# LoRaBBPi.net
KiCad netlist of a schematic drawn in EAGLE
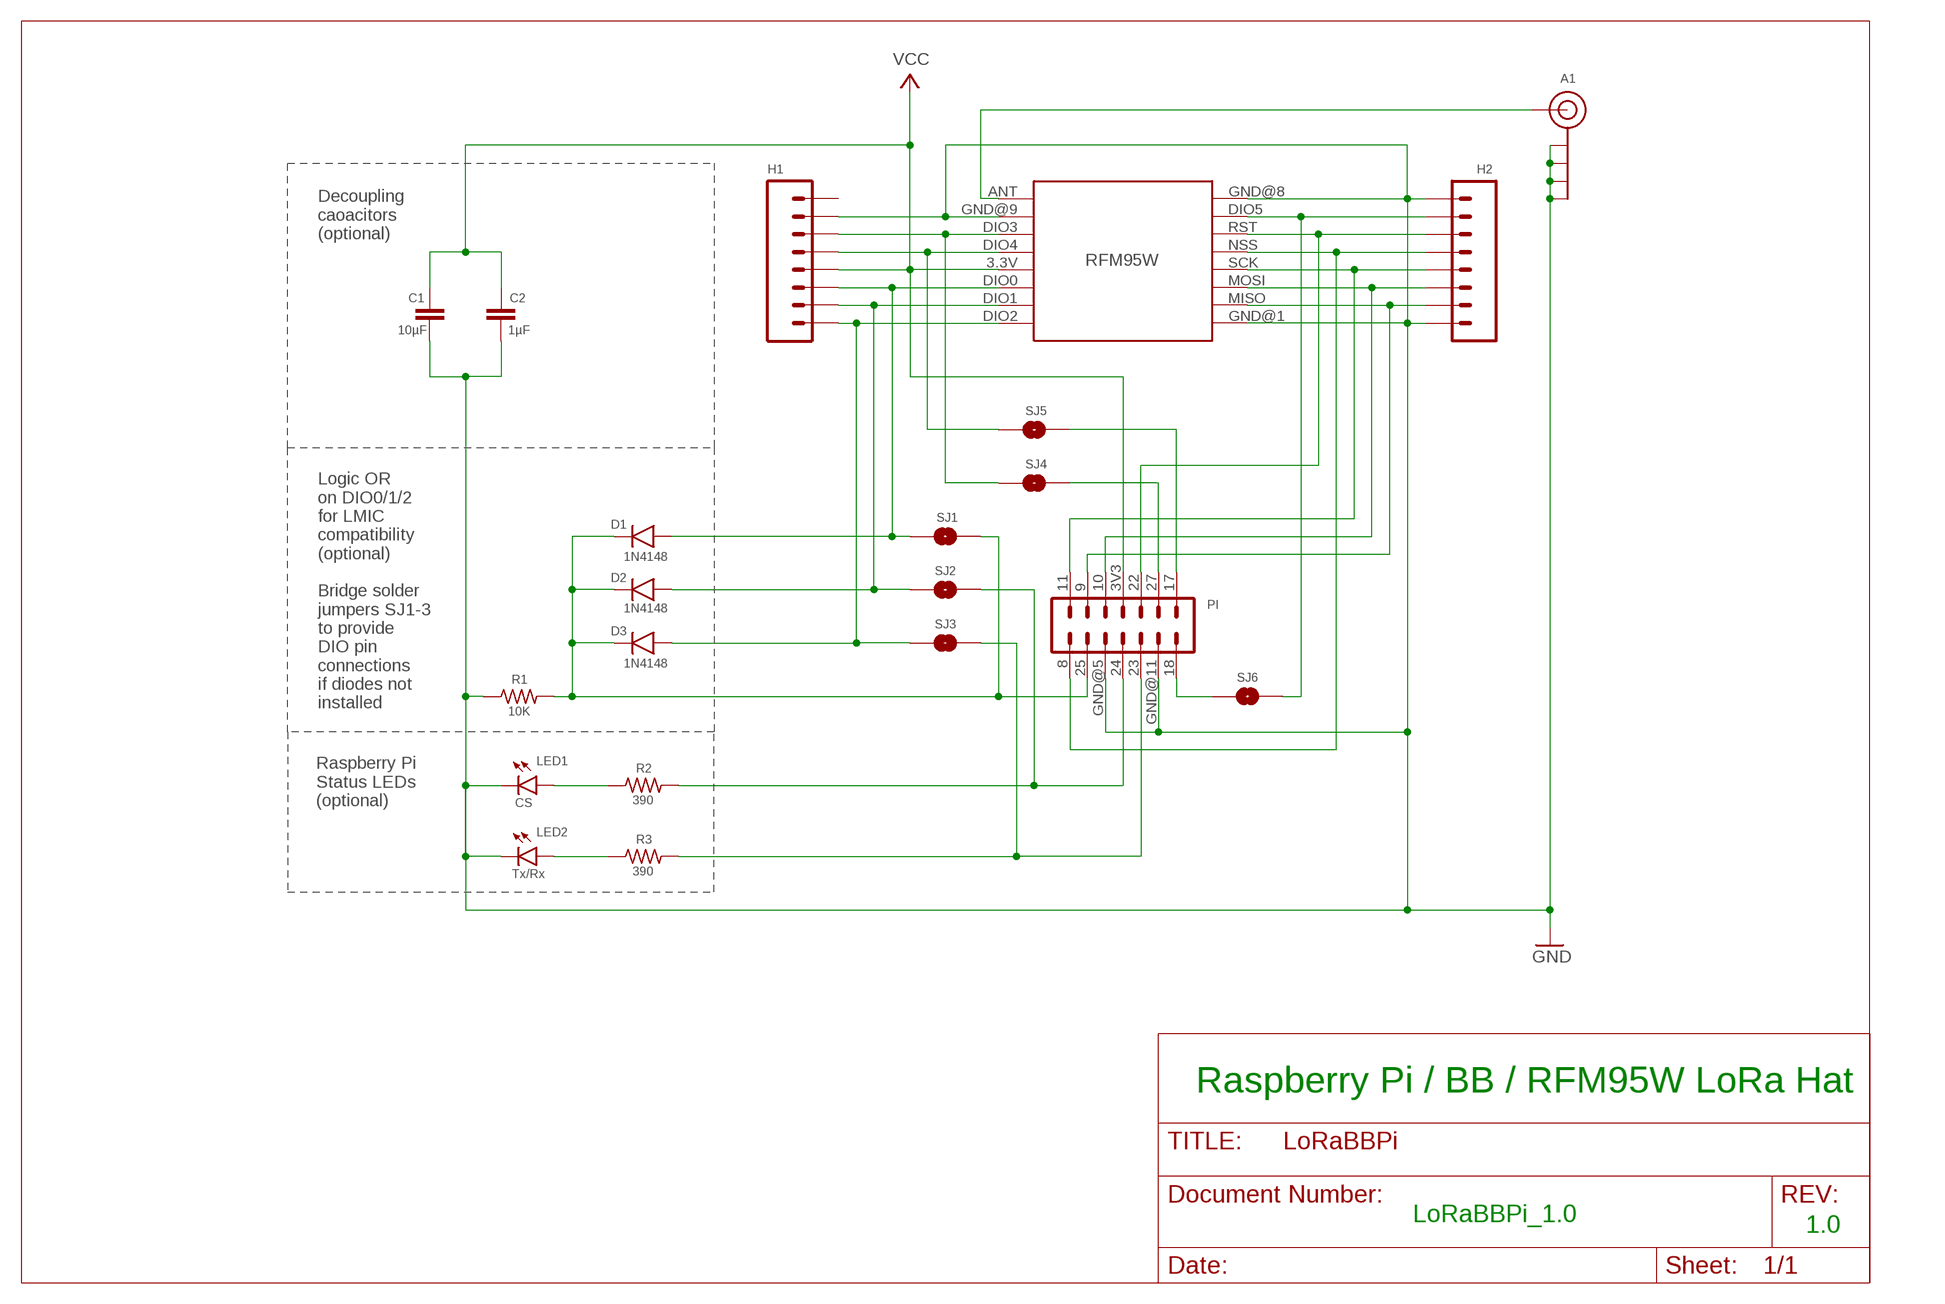
[diagram p0: schematic, sheet 1]

(export (version "E")
  (design (tool "Eeschema 10.0.6"))
  (components
    (comp (ref "A1")
      (value "U.FL-SMA-EDGE-COMBO")
      (footprint "eagle-import:U.FL-SMA-EDGE-COMBO")
      (libsource (lib "eagle-import") (part "U.FL-SMA-EDGE-COMBO"))
    )
    (comp (ref "C1")
      (value "10µF")
      (footprint "eagle-import:C0805")
      (libsource (lib "eagle-import") (part "CAPACITOR"))
    )
    (comp (ref "C2")
      (value "1µF")
      (footprint "eagle-import:C0805")
      (libsource (lib "eagle-import") (part "CAPACITOR"))
    )
    (comp (ref "D1")
      (value "1N4148")
      (footprint "eagle-import:SOD-123")
      (libsource (lib "eagle-import") (part "1N4148SMD"))
    )
    (comp (ref "D2")
      (value "1N4148")
      (footprint "eagle-import:SOD-123")
      (libsource (lib "eagle-import") (part "1N4148SMD"))
    )
    (comp (ref "D3")
      (value "1N4148")
      (footprint "eagle-import:SOD-123")
      (libsource (lib "eagle-import") (part "1N4148SMD"))
    )
    (comp (ref "H1")
      (value "1X8-PIN-HEADER")
      (footprint "eagle-import:1X8")
      (libsource (lib "eagle-import") (part "1X8-PIN-HEADER"))
    )
    (comp (ref "H2")
      (value "1X8-PIN-HEADER")
      (footprint "eagle-import:1X8")
      (libsource (lib "eagle-import") (part "1X8-PIN-HEADER"))
    )
    (comp (ref "LED1")
      (value "CS")
      (footprint "eagle-import:CHIP-LED0805")
      (libsource (lib "eagle-import") (part "LEDCHIP-LED0805"))
    )
    (comp (ref "LED2")
      (value "Tx/Rx")
      (footprint "eagle-import:CHIP-LED0805")
      (libsource (lib "eagle-import") (part "LEDCHIP-LED0805"))
    )
    (comp (ref "PI")
      (value "2X7-PIN-HEADER")
      (footprint "eagle-import:2X7")
      (libsource (lib "eagle-import") (part "2X7-PIN-HEADER"))
    )
    (comp (ref "R1")
      (value "10K")
      (footprint "eagle-import:R0805")
      (libsource (lib "eagle-import") (part "R-US_R0805"))
    )
    (comp (ref "R2")
      (value "390")
      (footprint "eagle-import:R0805")
      (libsource (lib "eagle-import") (part "R-US_R0805"))
    )
    (comp (ref "R3")
      (value "390")
      (footprint "eagle-import:R0805")
      (libsource (lib "eagle-import") (part "R-US_R0805"))
    )
    (comp (ref "RFM95W")
      (value "RFM95W-LORA")
      (footprint "eagle-import:RFM95W-LORA")
      (libsource (lib "eagle-import") (part "RFM95W-LORA"))
    )
    (comp (ref "SJ1") (value "SJ") (footprint "eagle-import:SJ") (libsource (lib "eagle-import") (part "SJ")))
    (comp (ref "SJ2") (value "SJ") (footprint "eagle-import:SJ") (libsource (lib "eagle-import") (part "SJ")))
    (comp (ref "SJ3") (value "SJ") (footprint "eagle-import:SJ") (libsource (lib "eagle-import") (part "SJ")))
    (comp (ref "SJ4") (value "SJ") (footprint "eagle-import:SJ") (libsource (lib "eagle-import") (part "SJ")))
    (comp (ref "SJ5") (value "SJ") (footprint "eagle-import:SJ") (libsource (lib "eagle-import") (part "SJ")))
    (comp (ref "SJ6") (value "SJ") (footprint "eagle-import:SJ") (libsource (lib "eagle-import") (part "SJ")))
  )
  (nets
    (net (code "1") (name "GND") (class "Default")
      (node (ref "A1") (pin "GND@1A") (pinfunction "GND_GND@1A") (pintype "bidirectional"))
      (node (ref "A1") (pin "GND@1B") (pinfunction "GND_GND@1B") (pintype "bidirectional"))
      (node (ref "A1") (pin "GND@2A") (pinfunction "GND_GND@2A") (pintype "bidirectional"))
      (node (ref "A1") (pin "GND@2B") (pinfunction "GND_GND@2B") (pintype "bidirectional"))
      (node (ref "C1") (pin "2") (pinfunction "2_2") (pintype "passive"))
      (node (ref "C2") (pin "2") (pinfunction "2_2") (pintype "passive"))
      (node (ref "H1") (pin "2") (pinfunction "2_2") (pintype "passive"))
      (node (ref "H2") (pin "1") (pinfunction "1_1") (pintype "passive"))
      (node (ref "H2") (pin "8") (pinfunction "8_8") (pintype "passive"))
      (node (ref "LED1") (pin "C") (pinfunction "C_C") (pintype "passive"))
      (node (ref "LED2") (pin "C") (pinfunction "C_C") (pintype "passive"))
      (node (ref "PI") (pin "GND@11") (pinfunction "GND_GND@11") (pintype "passive"))
      (node (ref "PI") (pin "GND@5") (pinfunction "GND_GND@5") (pintype "passive"))
      (node (ref "R1") (pin "1") (pinfunction "1_1") (pintype "passive"))
      (node (ref "RFM95W") (pin "GND@1") (pinfunction "GND.1_GND@1") (pintype "power_in"))
      (node (ref "RFM95W") (pin "GND@8") (pinfunction "GND.2_GND@8") (pintype "power_in"))
      (node (ref "RFM95W") (pin "GND@9") (pinfunction "GND.3_GND@9") (pintype "power_in"))
    )
    (net (code "2") (name "Net-(A1-PadSIG)") (class "Default")
      (node (ref "A1") (pin "SIG") (pinfunction "SIG_SIG") (pintype "bidirectional"))
      (node (ref "RFM95W") (pin "ANT") (pinfunction "ANT_ANT") (pintype "passive"))
    )
    (net (code "3") (name "Net-(D1-Pad1)") (class "Default")
      (node (ref "D1") (pin "1") (pinfunction "1_1") (pintype "bidirectional"))
      (node (ref "D2") (pin "1") (pinfunction "1_1") (pintype "bidirectional"))
      (node (ref "D3") (pin "1") (pinfunction "1_1") (pintype "bidirectional"))
      (node (ref "PI") (pin "25") (pinfunction "25_25") (pintype "passive"))
      (node (ref "R1") (pin "2") (pinfunction "2_2") (pintype "passive"))
      (node (ref "SJ1") (pin "2") (pinfunction "2_2") (pintype "passive"))
    )
    (net (code "4") (name "Net-(D1-Pad2)") (class "Default")
      (node (ref "D1") (pin "2") (pinfunction "2_2") (pintype "bidirectional"))
      (node (ref "H1") (pin "6") (pinfunction "6_6") (pintype "passive"))
      (node (ref "RFM95W") (pin "DIO0") (pinfunction "DIO0_DIO0") (pintype "bidirectional"))
      (node (ref "SJ1") (pin "1") (pinfunction "1_1") (pintype "passive"))
    )
    (net (code "5") (name "Net-(D2-Pad2)") (class "Default")
      (node (ref "D2") (pin "2") (pinfunction "2_2") (pintype "bidirectional"))
      (node (ref "H1") (pin "7") (pinfunction "7_7") (pintype "passive"))
      (node (ref "RFM95W") (pin "DIO1") (pinfunction "DIO1_DIO1") (pintype "bidirectional"))
      (node (ref "SJ2") (pin "1") (pinfunction "1_1") (pintype "passive"))
    )
    (net (code "6") (name "Net-(D3-Pad2)") (class "Default")
      (node (ref "D3") (pin "2") (pinfunction "2_2") (pintype "bidirectional"))
      (node (ref "H1") (pin "8") (pinfunction "8_8") (pintype "passive"))
      (node (ref "RFM95W") (pin "DIO2") (pinfunction "DIO2_DIO2") (pintype "bidirectional"))
      (node (ref "SJ3") (pin "1") (pinfunction "1_1") (pintype "passive"))
    )
    (net (code "7") (name "Net-(H1-Pad3)") (class "Default")
      (node (ref "H1") (pin "3") (pinfunction "3_3") (pintype "passive"))
      (node (ref "RFM95W") (pin "DIO3") (pinfunction "DIO3_DIO3") (pintype "bidirectional"))
      (node (ref "SJ4") (pin "1") (pinfunction "1_1") (pintype "passive"))
    )
    (net (code "8") (name "Net-(H1-Pad4)") (class "Default")
      (node (ref "H1") (pin "4") (pinfunction "4_4") (pintype "passive"))
      (node (ref "RFM95W") (pin "DIO4") (pinfunction "DIO4_DIO4") (pintype "bidirectional"))
      (node (ref "SJ5") (pin "1") (pinfunction "1_1") (pintype "passive"))
    )
    (net (code "9") (name "Net-(H2-Pad2)") (class "Default")
      (node (ref "H2") (pin "2") (pinfunction "2_2") (pintype "passive"))
      (node (ref "RFM95W") (pin "DIO5") (pinfunction "DIO5_DIO5") (pintype "bidirectional"))
      (node (ref "SJ6") (pin "2") (pinfunction "2_2") (pintype "passive"))
    )
    (net (code "10") (name "Net-(H2-Pad5)") (class "Default")
      (node (ref "H2") (pin "5") (pinfunction "5_5") (pintype "passive"))
      (node (ref "PI") (pin "11") (pinfunction "11_11") (pintype "passive"))
      (node (ref "RFM95W") (pin "SCK") (pinfunction "SCK_SCK") (pintype "bidirectional"))
    )
    (net (code "11") (name "Net-(H2-Pad6)") (class "Default")
      (node (ref "H2") (pin "6") (pinfunction "6_6") (pintype "passive"))
      (node (ref "PI") (pin "10") (pinfunction "10_10") (pintype "passive"))
      (node (ref "RFM95W") (pin "MOSI") (pinfunction "MOSI_MOSI") (pintype "bidirectional"))
    )
    (net (code "12") (name "Net-(H2-Pad7)") (class "Default")
      (node (ref "H2") (pin "7") (pinfunction "7_7") (pintype "passive"))
      (node (ref "PI") (pin "9") (pinfunction "9_9") (pintype "passive"))
      (node (ref "RFM95W") (pin "MISO") (pinfunction "MISO_MISO") (pintype "bidirectional"))
    )
    (net (code "13") (name "Net-(LED1-PadA)") (class "Default")
      (node (ref "LED1") (pin "A") (pinfunction "A_A") (pintype "passive"))
      (node (ref "R2") (pin "1") (pinfunction "1_1") (pintype "passive"))
    )
    (net (code "14") (name "Net-(LED2-PadA)") (class "Default")
      (node (ref "LED2") (pin "A") (pinfunction "A_A") (pintype "passive"))
      (node (ref "R3") (pin "1") (pinfunction "1_1") (pintype "passive"))
    )
    (net (code "15") (name "Net-(PI-1)") (class "Default")
      (node (ref "H2") (pin "4") (pinfunction "4_4") (pintype "passive"))
      (node (ref "PI") (pin "8") (pinfunction "1_8") (pintype "passive"))
      (node (ref "RFM95W") (pin "NSS") (pinfunction "NSS_NSS") (pintype "bidirectional"))
    )
    (net (code "16") (name "Net-(PI-22)") (class "Default")
      (node (ref "PI") (pin "27") (pinfunction "22_27") (pintype "passive"))
      (node (ref "SJ4") (pin "2") (pinfunction "2_2") (pintype "passive"))
    )
    (net (code "17") (name "Net-(PI-27)") (class "Default")
      (node (ref "H2") (pin "3") (pinfunction "3_3") (pintype "passive"))
      (node (ref "PI") (pin "22") (pinfunction "27_22") (pintype "passive"))
      (node (ref "RFM95W") (pin "RST") (pinfunction "RST_RST") (pintype "bidirectional"))
    )
    (net (code "18") (name "Net-(PI-Pad17)") (class "Default")
      (node (ref "PI") (pin "17") (pinfunction "17_17") (pintype "passive"))
      (node (ref "SJ5") (pin "2") (pinfunction "2_2") (pintype "passive"))
    )
    (net (code "19") (name "Net-(PI-Pad18)") (class "Default")
      (node (ref "PI") (pin "18") (pinfunction "18_18") (pintype "passive"))
      (node (ref "SJ6") (pin "1") (pinfunction "1_1") (pintype "passive"))
    )
    (net (code "20") (name "Net-(PI-Pad23)") (class "Default")
      (node (ref "PI") (pin "23") (pinfunction "23_23") (pintype "passive"))
      (node (ref "R3") (pin "2") (pinfunction "2_2") (pintype "passive"))
      (node (ref "SJ3") (pin "2") (pinfunction "2_2") (pintype "passive"))
    )
    (net (code "21") (name "Net-(PI-Pad24)") (class "Default")
      (node (ref "PI") (pin "24") (pinfunction "24_24") (pintype "passive"))
      (node (ref "R2") (pin "2") (pinfunction "2_2") (pintype "passive"))
      (node (ref "SJ2") (pin "2") (pinfunction "2_2") (pintype "passive"))
    )
    (net (code "22") (name "VCC") (class "Default")
      (node (ref "C1") (pin "1") (pinfunction "1_1") (pintype "passive"))
      (node (ref "C2") (pin "1") (pinfunction "1_1") (pintype "passive"))
      (node (ref "H1") (pin "5") (pinfunction "5_5") (pintype "passive"))
      (node (ref "PI") (pin "3V3") (pinfunction "3V3_3V3") (pintype "passive"))
      (node (ref "RFM95W") (pin "3.3V") (pinfunction "3.3V_3.3V") (pintype "power_in"))
    )
    (net (code "23") (name "unconnected-(H1-Pad1)") (class "Default")
      (node (ref "H1") (pin "1") (pinfunction "1_1") (pintype "passive"))
    )
  )
)
